# Cores_POWER.net
KiCad netlist of a schematic drawn in Altium Designer
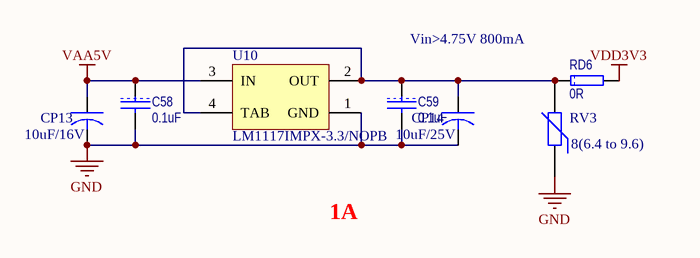
[diagram p0: Cores POWER.SchDoc]

(export (version "E")
  (design (tool "Eeschema 10.0.6"))
  (components
    (comp (ref "C58")
      (value "0.1uF")
      (footprint "1608[0603]")
      (description "Capacitor")
      (fields (field (name "MANUFACTURER") "TDK"))
      (libsource (lib "*") (part "CAP"))
    )
    (comp (ref "C59")
      (value "0.1uF")
      (footprint "1608[0603]")
      (description "Capacitor")
      (fields (field (name "MANUFACTURER") "TDK"))
      (libsource (lib "*") (part "CAP"))
    )
    (comp (ref "CP13")
      (value "10uF/16V")
      (footprint "3216[1206]")
      (description "Tantalum Capacitor")
      (libsource (lib "*") (part "CAPACITOR"))
    )
    (comp (ref "CP14")
      (value "10uF/25V")
      (footprint "6032[2312]CC")
      (description "Tantalum Capacitor")
      (libsource (lib "*") (part "CAPACITOR"))
    )
    (comp (ref "RD6")
      (value "0R")
      (footprint "1608[0603]RD")
      (description "RES")
      (fields (field (name "MANUFACTURER") "vishay"))
      (libsource (lib "*") (part "RES"))
    )
    (comp (ref "RV3")
      (value "8(6.4 to 9.6)")
      (footprint "1608[0603]RV")
      (description "压敏电阻")
      (fields (field (name "PUBLISHER") "Altium Limited"))
      (libsource (lib "Miscellaneous Devices") (part "Res Varistor"))
    )
    (comp (ref "U10")
      (value "LM1117IMPX-3.3/NOPB")
      (footprint "MP04A_N")
      (description "800mA Low-Dropout Linear Regulator, 4-pin SOT-223, Pb-Free")
      (fields
        (field (name "PARTNUMBER") "LM1117MPX-3.3/NOPB")
        (field (name "MANUFACTURER") "National Semiconductor")
        (field (name "PUBLISHER") "Altium Limited")
      )
      (libsource (lib "NSC LDO") (part "LM1117MPX-3.3/NOPB"))
    )
  )
  (nets
    (net (code "1") (name "GND") (class "Default")
      (node (ref "C58") (pin "2") (pinfunction "2_2") (pintype "passive"))
      (node (ref "C59") (pin "2") (pinfunction "2_2") (pintype "passive"))
      (node (ref "CP13") (pin "2") (pinfunction "2_2") (pintype "passive"))
      (node (ref "CP14") (pin "2") (pinfunction "2_2") (pintype "passive"))
      (node (ref "RV3") (pin "1") (pinfunction "1_1") (pintype "passive"))
      (node (ref "U10") (pin "1") (pinfunction "GND_1") (pintype "power_in"))
    )
    (net (code "2") (name "Net-(U10-OUT)") (class "Default")
      (node (ref "C59") (pin "1") (pinfunction "1_1") (pintype "passive"))
      (node (ref "CP14") (pin "1") (pinfunction "1_1") (pintype "passive"))
      (node (ref "RD6") (pin "1") (pinfunction "1_1") (pintype "passive"))
      (node (ref "RV3") (pin "2") (pinfunction "2_2") (pintype "passive"))
      (node (ref "U10") (pin "2") (pinfunction "OUT_2") (pintype "power_in"))
      (node (ref "U10") (pin "4") (pinfunction "TAB_4") (pintype "power_in"))
    )
    (net (code "3") (name "VAA5V") (class "Default")
      (node (ref "C58") (pin "1") (pinfunction "1_1") (pintype "passive"))
      (node (ref "CP13") (pin "1") (pinfunction "1_1") (pintype "passive"))
      (node (ref "U10") (pin "3") (pinfunction "IN_3") (pintype "power_in"))
    )
    (net (code "4") (name "VDD3V3") (class "Default")
      (node (ref "RD6") (pin "2") (pinfunction "2_2") (pintype "passive"))
    )
  )
)
